# heater_board.net
KiCad netlist of a schematic drawn in EAGLE
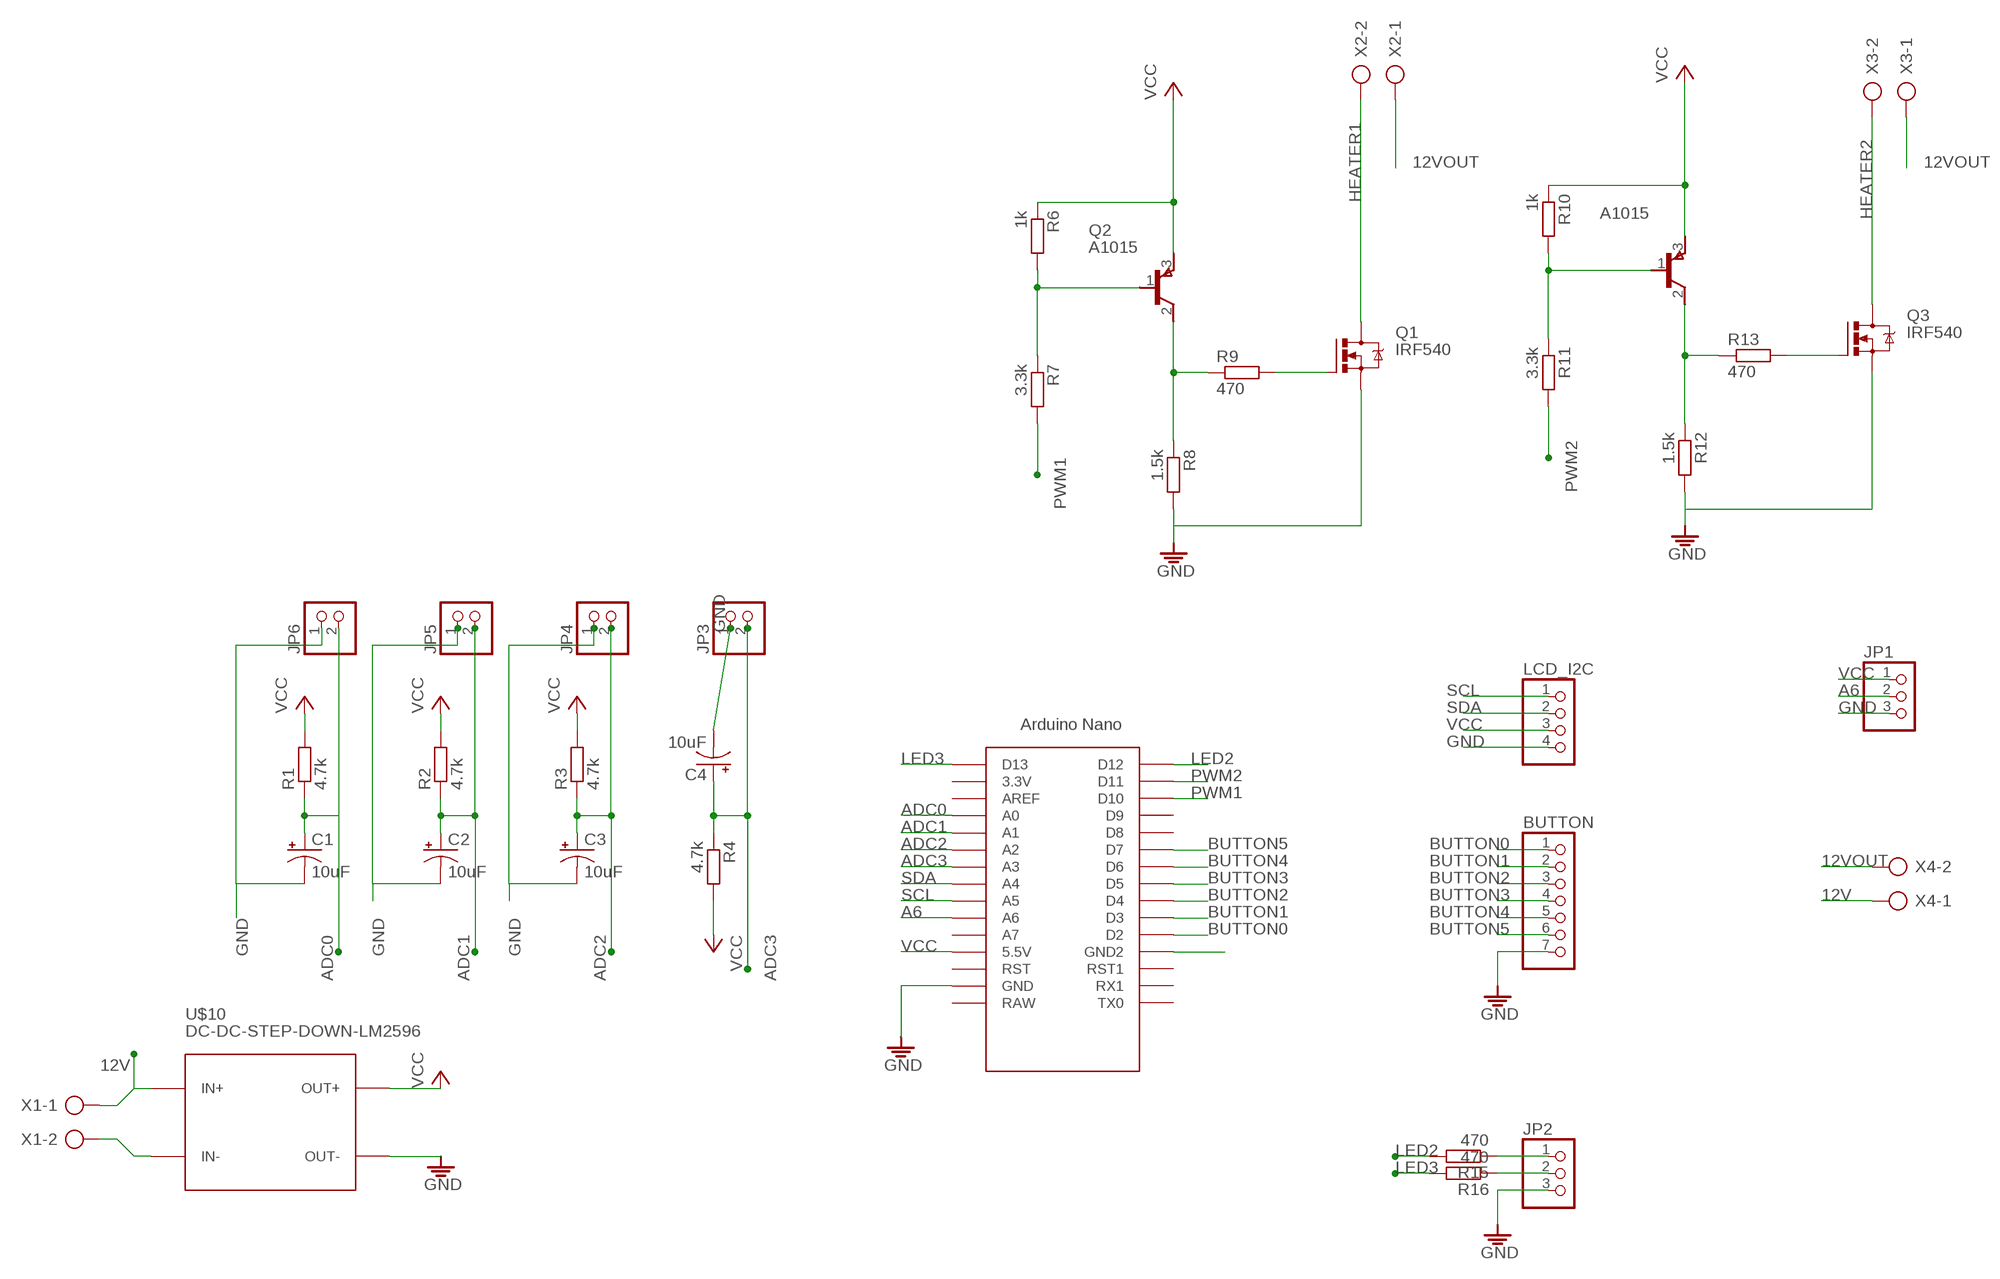
[diagram p0: schematic, sheet 1]

(export (version "E")
  (design (tool "Eeschema 10.0.6"))
  (components
    (comp (ref "A1015")
      (value "A1015")
      (footprint "eagle-import:TO92L")
      (libsource (lib "eagle-import") (part "A1015"))
    )
    (comp (ref "BUTTON")
      (value "PINHD-1X7")
      (footprint "eagle-import:1X07")
      (libsource (lib "eagle-import") (part "PINHD-1X7"))
    )
    (comp (ref "C1")
      (value "10uF")
      (footprint "eagle-import:E2,5-5")
      (libsource (lib "eagle-import") (part "CPOL-USE2.5-5"))
    )
    (comp (ref "C2")
      (value "10uF")
      (footprint "eagle-import:E2,5-5")
      (libsource (lib "eagle-import") (part "CPOL-USE2.5-5"))
    )
    (comp (ref "C3")
      (value "10uF")
      (footprint "eagle-import:E2,5-5")
      (libsource (lib "eagle-import") (part "CPOL-USE2.5-5"))
    )
    (comp (ref "C4")
      (value "10uF")
      (footprint "eagle-import:E2,5-5")
      (libsource (lib "eagle-import") (part "CPOL-USE2.5-5"))
    )
    (comp (ref "JP1")
      (value "PINHD-1X3")
      (footprint "eagle-import:1X03")
      (libsource (lib "eagle-import") (part "PINHD-1X3"))
    )
    (comp (ref "JP2")
      (value "PINHD-1X3")
      (footprint "eagle-import:1X03")
      (libsource (lib "eagle-import") (part "PINHD-1X3"))
    )
    (comp (ref "JP3")
      (value "PINHD-1X2")
      (footprint "eagle-import:1X02")
      (libsource (lib "eagle-import") (part "PINHD-1X2"))
    )
    (comp (ref "JP4")
      (value "PINHD-1X2")
      (footprint "eagle-import:1X02")
      (libsource (lib "eagle-import") (part "PINHD-1X2"))
    )
    (comp (ref "JP5")
      (value "PINHD-1X2")
      (footprint "eagle-import:1X02")
      (libsource (lib "eagle-import") (part "PINHD-1X2"))
    )
    (comp (ref "JP6")
      (value "PINHD-1X2")
      (footprint "eagle-import:1X02")
      (libsource (lib "eagle-import") (part "PINHD-1X2"))
    )
    (comp (ref "LCD_I2C")
      (value "PINHD-1X4")
      (footprint "eagle-import:1X04")
      (libsource (lib "eagle-import") (part "PINHD-1X4"))
    )
    (comp (ref "Q1")
      (value "IRF540")
      (footprint "eagle-import:TO220BV")
      (libsource (lib "eagle-import") (part "IRF540"))
    )
    (comp (ref "Q2")
      (value "A1015")
      (footprint "eagle-import:TO92L")
      (libsource (lib "eagle-import") (part "A1015"))
    )
    (comp (ref "Q3")
      (value "IRF540")
      (footprint "eagle-import:TO220BV")
      (libsource (lib "eagle-import") (part "IRF540"))
    )
    (comp (ref "R1")
      (value "4.7k")
      (footprint "eagle-import:0207_10")
      (libsource (lib "eagle-import") (part "R-EU_0207/10"))
    )
    (comp (ref "R2")
      (value "4.7k")
      (footprint "eagle-import:0207_10")
      (libsource (lib "eagle-import") (part "R-EU_0207/10"))
    )
    (comp (ref "R3")
      (value "4.7k")
      (footprint "eagle-import:0207_10")
      (libsource (lib "eagle-import") (part "R-EU_0207/10"))
    )
    (comp (ref "R4")
      (value "4.7k")
      (footprint "eagle-import:0207_10")
      (libsource (lib "eagle-import") (part "R-EU_0207/10"))
    )
    (comp (ref "R6")
      (value "1k")
      (footprint "eagle-import:0207_10")
      (libsource (lib "eagle-import") (part "R-EU_0207/10"))
    )
    (comp (ref "R7")
      (value "3.3k")
      (footprint "eagle-import:0207_10")
      (libsource (lib "eagle-import") (part "R-EU_0207/10"))
    )
    (comp (ref "R8")
      (value "1.5k")
      (footprint "eagle-import:0207_10")
      (libsource (lib "eagle-import") (part "R-EU_0207/10"))
    )
    (comp (ref "R9")
      (value "470")
      (footprint "eagle-import:0207_10")
      (libsource (lib "eagle-import") (part "R-EU_0207/10"))
    )
    (comp (ref "R10")
      (value "1k")
      (footprint "eagle-import:0207_10")
      (libsource (lib "eagle-import") (part "R-EU_0207/10"))
    )
    (comp (ref "R11")
      (value "3.3k")
      (footprint "eagle-import:0207_10")
      (libsource (lib "eagle-import") (part "R-EU_0207/10"))
    )
    (comp (ref "R12")
      (value "1.5k")
      (footprint "eagle-import:0207_10")
      (libsource (lib "eagle-import") (part "R-EU_0207/10"))
    )
    (comp (ref "R13")
      (value "470")
      (footprint "eagle-import:0207_10")
      (libsource (lib "eagle-import") (part "R-EU_0207/10"))
    )
    (comp (ref "R15")
      (value "470")
      (footprint "eagle-import:0207_10")
      (libsource (lib "eagle-import") (part "R-EU_0207/10"))
    )
    (comp (ref "R16")
      (value "470")
      (footprint "eagle-import:0207_10")
      (libsource (lib "eagle-import") (part "R-EU_0207/10"))
    )
    (comp (ref "U$1")
      (value "NANO")
      (footprint "eagle-import:NANO")
      (libsource (lib "eagle-import") (part "NANO"))
    )
    (comp (ref "U$10")
      (value "DC-DC-STEP-DOWN-LM2596")
      (footprint "eagle-import:DC-DC-STEP-DOWN-LM2596")
      (libsource (lib "eagle-import") (part "DC-DC-STEP-DOWN-LM2596"))
    )
    (comp (ref "X1")
      (value "AK300/2")
      (footprint "eagle-import:AK300_2")
      (libsource (lib "eagle-import") (part "AK300/2"))
    )
    (comp (ref "X2")
      (value "AK300/2")
      (footprint "eagle-import:AK300_2")
      (libsource (lib "eagle-import") (part "AK300/2"))
    )
    (comp (ref "X3")
      (value "AK300/2")
      (footprint "eagle-import:AK300_2")
      (libsource (lib "eagle-import") (part "AK300/2"))
    )
    (comp (ref "X4")
      (value "AK300/2")
      (footprint "eagle-import:AK300_2")
      (libsource (lib "eagle-import") (part "AK300/2"))
    )
  )
  (nets
    (net (code "1") (name "/12V") (class "Default")
      (node (ref "U$10") (pin "IN+") (pinfunction "IN+_IN+") (pintype "bidirectional"))
      (node (ref "X1") (pin "1") (pinfunction "KL_1") (pintype "passive"))
      (node (ref "X4") (pin "1") (pinfunction "KL_1") (pintype "passive"))
    )
    (net (code "2") (name "/12VOUT") (class "Default")
      (node (ref "X2") (pin "1") (pinfunction "KL_1") (pintype "passive"))
      (node (ref "X3") (pin "1") (pinfunction "KL_1") (pintype "passive"))
      (node (ref "X4") (pin "2") (pinfunction "KL_2") (pintype "passive"))
    )
    (net (code "3") (name "/A6") (class "Default")
      (node (ref "JP1") (pin "2") (pinfunction "2_2") (pintype "passive"))
      (node (ref "U$1") (pin "A6") (pinfunction "A6_A6") (pintype "bidirectional"))
    )
    (net (code "4") (name "/ADC0") (class "Default")
      (node (ref "C1") (pin "+") (pinfunction "+_+") (pintype "passive"))
      (node (ref "JP6") (pin "2") (pinfunction "2_2") (pintype "passive"))
      (node (ref "R1") (pin "1") (pinfunction "1_1") (pintype "passive"))
      (node (ref "U$1") (pin "A0") (pinfunction "A0_A0") (pintype "bidirectional"))
    )
    (net (code "5") (name "/ADC1") (class "Default")
      (node (ref "C2") (pin "+") (pinfunction "+_+") (pintype "passive"))
      (node (ref "JP5") (pin "2") (pinfunction "2_2") (pintype "passive"))
      (node (ref "R2") (pin "1") (pinfunction "1_1") (pintype "passive"))
      (node (ref "U$1") (pin "A1") (pinfunction "A1_A1") (pintype "bidirectional"))
    )
    (net (code "6") (name "/ADC2") (class "Default")
      (node (ref "C3") (pin "+") (pinfunction "+_+") (pintype "passive"))
      (node (ref "JP4") (pin "2") (pinfunction "2_2") (pintype "passive"))
      (node (ref "R3") (pin "1") (pinfunction "1_1") (pintype "passive"))
      (node (ref "U$1") (pin "A2") (pinfunction "A2_A2") (pintype "bidirectional"))
    )
    (net (code "7") (name "/ADC3") (class "Default")
      (node (ref "C4") (pin "+") (pinfunction "+_+") (pintype "passive"))
      (node (ref "JP3") (pin "2") (pinfunction "2_2") (pintype "passive"))
      (node (ref "R4") (pin "1") (pinfunction "1_1") (pintype "passive"))
      (node (ref "U$1") (pin "A3") (pinfunction "A3_A3") (pintype "bidirectional"))
    )
    (net (code "8") (name "/BUTTON0") (class "Default")
      (node (ref "BUTTON") (pin "1") (pinfunction "1_1") (pintype "passive"))
      (node (ref "U$1") (pin "D2") (pinfunction "D2_D2") (pintype "bidirectional"))
    )
    (net (code "9") (name "/BUTTON1") (class "Default")
      (node (ref "BUTTON") (pin "2") (pinfunction "2_2") (pintype "passive"))
      (node (ref "U$1") (pin "D3") (pinfunction "D3_D3") (pintype "bidirectional"))
    )
    (net (code "10") (name "/BUTTON2") (class "Default")
      (node (ref "BUTTON") (pin "3") (pinfunction "3_3") (pintype "passive"))
      (node (ref "U$1") (pin "D4") (pinfunction "D4_D4") (pintype "bidirectional"))
    )
    (net (code "11") (name "/BUTTON3") (class "Default")
      (node (ref "BUTTON") (pin "4") (pinfunction "4_4") (pintype "passive"))
      (node (ref "U$1") (pin "D5") (pinfunction "D5_D5") (pintype "bidirectional"))
    )
    (net (code "12") (name "/BUTTON4") (class "Default")
      (node (ref "BUTTON") (pin "5") (pinfunction "5_5") (pintype "passive"))
      (node (ref "U$1") (pin "D6") (pinfunction "D6_D6") (pintype "bidirectional"))
    )
    (net (code "13") (name "/BUTTON5") (class "Default")
      (node (ref "BUTTON") (pin "6") (pinfunction "6_6") (pintype "passive"))
      (node (ref "U$1") (pin "D7") (pinfunction "D7_D7") (pintype "bidirectional"))
    )
    (net (code "14") (name "/HEATER1") (class "Default")
      (node (ref "Q1") (pin "D") (pinfunction "D_D") (pintype "passive"))
      (node (ref "X2") (pin "2") (pinfunction "KL_2") (pintype "passive"))
    )
    (net (code "15") (name "/HEATER2") (class "Default")
      (node (ref "Q3") (pin "D") (pinfunction "D_D") (pintype "passive"))
      (node (ref "X3") (pin "2") (pinfunction "KL_2") (pintype "passive"))
    )
    (net (code "16") (name "/LED2") (class "Default")
      (node (ref "R15") (pin "2") (pinfunction "2_2") (pintype "passive"))
      (node (ref "U$1") (pin "D12") (pinfunction "D12_D12") (pintype "bidirectional"))
    )
    (net (code "17") (name "/LED3") (class "Default")
      (node (ref "R16") (pin "2") (pinfunction "2_2") (pintype "passive"))
      (node (ref "U$1") (pin "D13") (pinfunction "D13_D13") (pintype "bidirectional"))
    )
    (net (code "18") (name "/PWM1") (class "Default")
      (node (ref "R7") (pin "2") (pinfunction "2_2") (pintype "passive"))
      (node (ref "U$1") (pin "D10") (pinfunction "D10_D10") (pintype "bidirectional"))
    )
    (net (code "19") (name "/PWM2") (class "Default")
      (node (ref "R11") (pin "2") (pinfunction "2_2") (pintype "passive"))
      (node (ref "U$1") (pin "D11") (pinfunction "D11_D11") (pintype "bidirectional"))
    )
    (net (code "20") (name "/SCL") (class "Default")
      (node (ref "LCD_I2C") (pin "1") (pinfunction "1_1") (pintype "passive"))
      (node (ref "U$1") (pin "A5") (pinfunction "A5_A5") (pintype "bidirectional"))
    )
    (net (code "21") (name "/SDA") (class "Default")
      (node (ref "LCD_I2C") (pin "2") (pinfunction "2_2") (pintype "passive"))
      (node (ref "U$1") (pin "A4") (pinfunction "A4_A4") (pintype "bidirectional"))
    )
    (net (code "22") (name "GND") (class "Default")
      (node (ref "BUTTON") (pin "7") (pinfunction "7_7") (pintype "passive"))
      (node (ref "C1") (pin "-") (pinfunction "-_-") (pintype "passive"))
      (node (ref "C2") (pin "-") (pinfunction "-_-") (pintype "passive"))
      (node (ref "C3") (pin "-") (pinfunction "-_-") (pintype "passive"))
      (node (ref "C4") (pin "-") (pinfunction "-_-") (pintype "passive"))
      (node (ref "JP1") (pin "3") (pinfunction "3_3") (pintype "passive"))
      (node (ref "JP2") (pin "3") (pinfunction "3_3") (pintype "passive"))
      (node (ref "JP3") (pin "1") (pinfunction "1_1") (pintype "passive"))
      (node (ref "JP4") (pin "1") (pinfunction "1_1") (pintype "passive"))
      (node (ref "JP5") (pin "1") (pinfunction "1_1") (pintype "passive"))
      (node (ref "JP6") (pin "1") (pinfunction "1_1") (pintype "passive"))
      (node (ref "LCD_I2C") (pin "4") (pinfunction "4_4") (pintype "passive"))
      (node (ref "Q1") (pin "S") (pinfunction "S_S") (pintype "passive"))
      (node (ref "Q3") (pin "S") (pinfunction "S_S") (pintype "passive"))
      (node (ref "R12") (pin "2") (pinfunction "2_2") (pintype "passive"))
      (node (ref "R8") (pin "2") (pinfunction "2_2") (pintype "passive"))
      (node (ref "U$1") (pin "GND") (pinfunction "GND_GND") (pintype "bidirectional"))
      (node (ref "U$1") (pin "GND1") (pinfunction "GND2_GND1") (pintype "bidirectional"))
      (node (ref "U$10") (pin "IN-") (pinfunction "IN-_IN-") (pintype "bidirectional"))
      (node (ref "U$10") (pin "OUT-") (pinfunction "OUT-_OUT-") (pintype "bidirectional"))
      (node (ref "X1") (pin "2") (pinfunction "KL_2") (pintype "passive"))
    )
    (net (code "23") (name "Net-(A1015-B)") (class "Default")
      (node (ref "A1015") (pin "1") (pinfunction "B_1") (pintype "passive"))
      (node (ref "R10") (pin "2") (pinfunction "2_2") (pintype "passive"))
      (node (ref "R11") (pin "1") (pinfunction "1_1") (pintype "passive"))
    )
    (net (code "24") (name "Net-(A1015-C)") (class "Default")
      (node (ref "A1015") (pin "2") (pinfunction "C_2") (pintype "passive"))
      (node (ref "R12") (pin "1") (pinfunction "1_1") (pintype "passive"))
      (node (ref "R13") (pin "1") (pinfunction "1_1") (pintype "passive"))
    )
    (net (code "25") (name "Net-(JP2-Pad1)") (class "Default")
      (node (ref "JP2") (pin "1") (pinfunction "1_1") (pintype "passive"))
      (node (ref "R15") (pin "1") (pinfunction "1_1") (pintype "passive"))
    )
    (net (code "26") (name "Net-(JP2-Pad2)") (class "Default")
      (node (ref "JP2") (pin "2") (pinfunction "2_2") (pintype "passive"))
      (node (ref "R16") (pin "1") (pinfunction "1_1") (pintype "passive"))
    )
    (net (code "27") (name "Net-(Q1-PadG)") (class "Default")
      (node (ref "Q1") (pin "G") (pinfunction "G_G") (pintype "passive"))
      (node (ref "R9") (pin "2") (pinfunction "2_2") (pintype "passive"))
    )
    (net (code "28") (name "Net-(Q2-B)") (class "Default")
      (node (ref "Q2") (pin "1") (pinfunction "B_1") (pintype "passive"))
      (node (ref "R6") (pin "2") (pinfunction "2_2") (pintype "passive"))
      (node (ref "R7") (pin "1") (pinfunction "1_1") (pintype "passive"))
    )
    (net (code "29") (name "Net-(Q2-C)") (class "Default")
      (node (ref "Q2") (pin "2") (pinfunction "C_2") (pintype "passive"))
      (node (ref "R8") (pin "1") (pinfunction "1_1") (pintype "passive"))
      (node (ref "R9") (pin "1") (pinfunction "1_1") (pintype "passive"))
    )
    (net (code "30") (name "Net-(Q3-PadG)") (class "Default")
      (node (ref "Q3") (pin "G") (pinfunction "G_G") (pintype "passive"))
      (node (ref "R13") (pin "2") (pinfunction "2_2") (pintype "passive"))
    )
    (net (code "31") (name "VCC") (class "Default")
      (node (ref "A1015") (pin "3") (pinfunction "E_3") (pintype "passive"))
      (node (ref "JP1") (pin "1") (pinfunction "1_1") (pintype "passive"))
      (node (ref "LCD_I2C") (pin "3") (pinfunction "3_3") (pintype "passive"))
      (node (ref "Q2") (pin "3") (pinfunction "E_3") (pintype "passive"))
      (node (ref "R1") (pin "2") (pinfunction "2_2") (pintype "passive"))
      (node (ref "R10") (pin "1") (pinfunction "1_1") (pintype "passive"))
      (node (ref "R2") (pin "2") (pinfunction "2_2") (pintype "passive"))
      (node (ref "R3") (pin "2") (pinfunction "2_2") (pintype "passive"))
      (node (ref "R4") (pin "2") (pinfunction "2_2") (pintype "passive"))
      (node (ref "R6") (pin "1") (pinfunction "1_1") (pintype "passive"))
      (node (ref "U$1") (pin "5V") (pinfunction "5.5V_5V") (pintype "bidirectional"))
      (node (ref "U$10") (pin "OUT+") (pinfunction "OUT+_OUT+") (pintype "bidirectional"))
    )
    (net (code "32") (name "unconnected-(U$1-Pad3.3V)") (class "Default")
      (node (ref "U$1") (pin "3.3V") (pinfunction "3.3V_3.3V") (pintype "bidirectional"))
    )
    (net (code "33") (name "unconnected-(U$1-PadA7)") (class "Default")
      (node (ref "U$1") (pin "A7") (pinfunction "A7_A7") (pintype "bidirectional"))
    )
    (net (code "34") (name "unconnected-(U$1-PadAREF)") (class "Default")
      (node (ref "U$1") (pin "AREF") (pinfunction "AREF_AREF") (pintype "bidirectional"))
    )
    (net (code "35") (name "unconnected-(U$1-PadD8)") (class "Default")
      (node (ref "U$1") (pin "D8") (pinfunction "D8_D8") (pintype "bidirectional"))
    )
    (net (code "36") (name "unconnected-(U$1-PadD9)") (class "Default")
      (node (ref "U$1") (pin "D9") (pinfunction "D9_D9") (pintype "bidirectional"))
    )
    (net (code "37") (name "unconnected-(U$1-PadICSP1)") (class "Default")
      (node (ref "U$1") (pin "ICSP1") (pinfunction "ICSP1_ICSP1") (pintype "bidirectional"))
    )
    (net (code "38") (name "unconnected-(U$1-PadICSP2)") (class "Default")
      (node (ref "U$1") (pin "ICSP2") (pinfunction "ICSP2_ICSP2") (pintype "bidirectional"))
    )
    (net (code "39") (name "unconnected-(U$1-PadICSP3)") (class "Default")
      (node (ref "U$1") (pin "ICSP3") (pinfunction "ICSP3_ICSP3") (pintype "bidirectional"))
    )
    (net (code "40") (name "unconnected-(U$1-PadICSP4)") (class "Default")
      (node (ref "U$1") (pin "ICSP4") (pinfunction "ICSP4_ICSP4") (pintype "bidirectional"))
    )
    (net (code "41") (name "unconnected-(U$1-PadICSP5)") (class "Default")
      (node (ref "U$1") (pin "ICSP5") (pinfunction "ICSP5_ICSP5") (pintype "bidirectional"))
    )
    (net (code "42") (name "unconnected-(U$1-PadICSP6)") (class "Default")
      (node (ref "U$1") (pin "ICSP6") (pinfunction "ICSP6_ICSP6") (pintype "bidirectional"))
    )
    (net (code "43") (name "unconnected-(U$1-PadRAW)") (class "Default")
      (node (ref "U$1") (pin "RAW") (pinfunction "RAW_RAW") (pintype "bidirectional"))
    )
    (net (code "44") (name "unconnected-(U$1-PadRST)") (class "Default")
      (node (ref "U$1") (pin "RST") (pinfunction "RST_RST") (pintype "bidirectional"))
    )
    (net (code "45") (name "unconnected-(U$1-PadRST1)") (class "Default")
      (node (ref "U$1") (pin "RST1") (pinfunction "RST1_RST1") (pintype "bidirectional"))
    )
    (net (code "46") (name "unconnected-(U$1-PadRX1)") (class "Default")
      (node (ref "U$1") (pin "RX1") (pinfunction "RX1_RX1") (pintype "bidirectional"))
    )
    (net (code "47") (name "unconnected-(U$1-PadTX0)") (class "Default")
      (node (ref "U$1") (pin "TX0") (pinfunction "TX0_TX0") (pintype "bidirectional"))
    )
  )
)
